# car2.net
KiCad netlist of a schematic drawn in Altium Designer
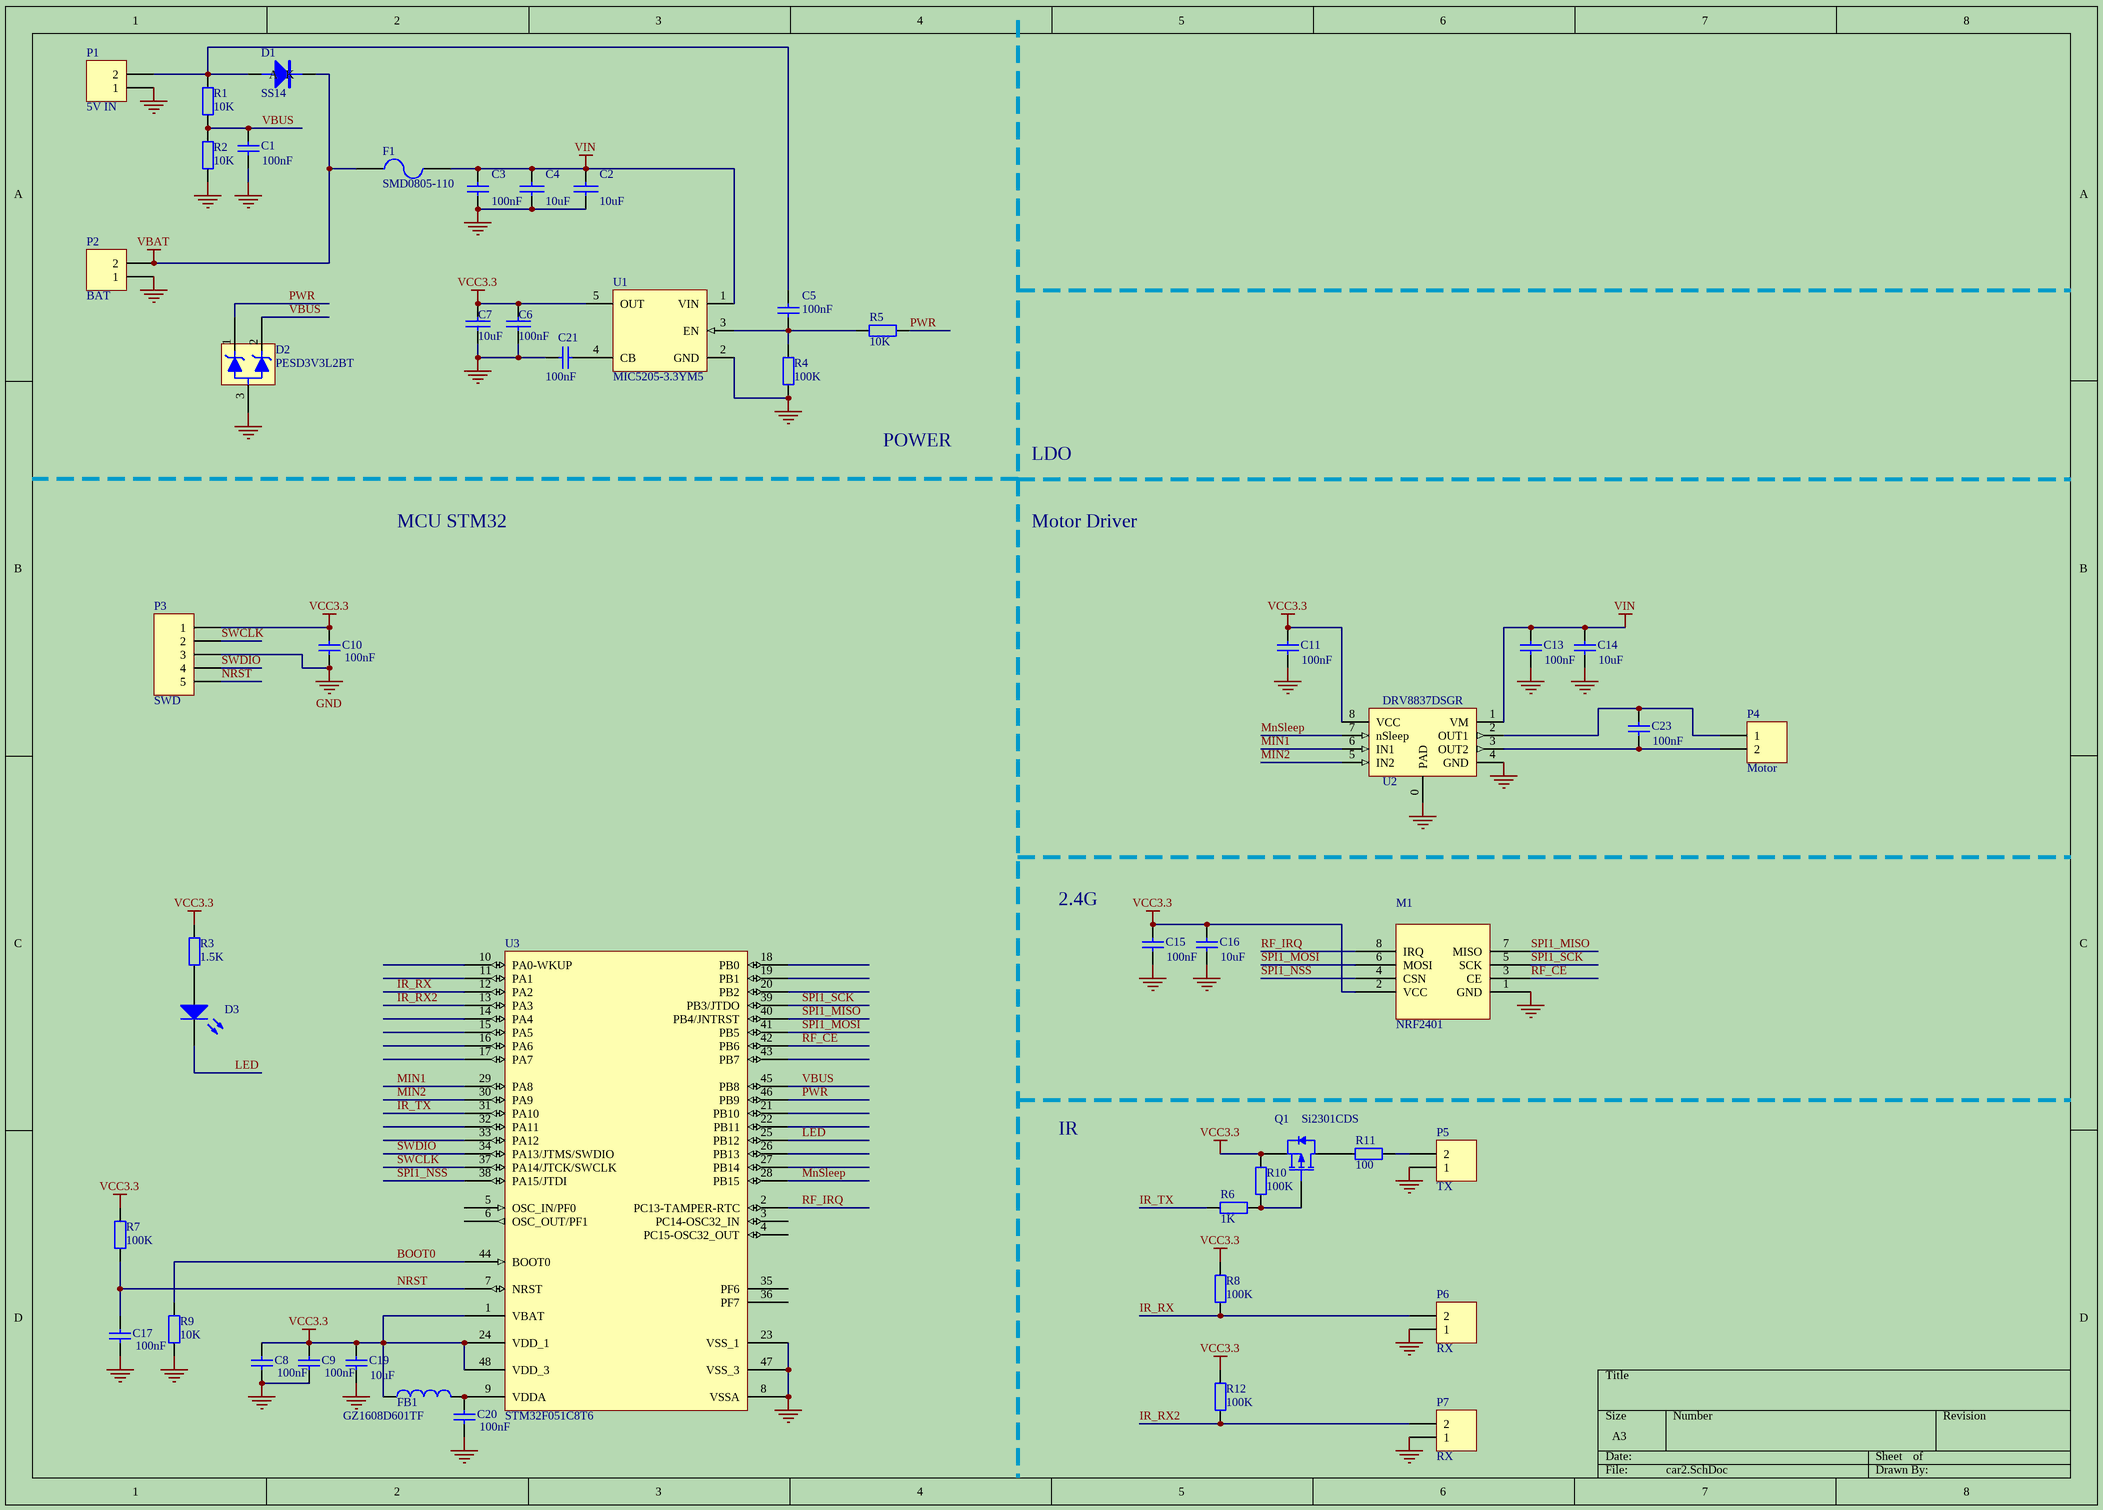
[diagram p0: car2.SchDoc]

(export (version "E")
  (design (tool "Eeschema 10.0.6"))
  (components
    (comp (ref "C1")
      (value "100nF")
      (footprint "C0603")
      (description "Capacitor")
      (fields (field (name "PUBLISHER") "Altium Limited"))
      (libsource (lib "Miscellaneous Devices") (part "Cap"))
    )
    (comp (ref "C2")
      (value "10uF")
      (footprint "C0805")
      (description "Capacitor")
      (libsource (lib "*") (part "CAP"))
    )
    (comp (ref "C3")
      (value "100nF")
      (footprint "C0603")
      (description "Capacitor")
      (fields (field (name "PUBLISHER") "Altium Limited"))
      (libsource (lib "Miscellaneous Devices") (part "Cap"))
    )
    (comp (ref "C4")
      (value "10uF")
      (footprint "C0805")
      (description "Capacitor")
      (libsource (lib "*") (part "CAP"))
    )
    (comp (ref "C5")
      (value "100nF")
      (footprint "C0603")
      (description "Capacitor")
      (fields (field (name "PUBLISHER") "Altium Limited"))
      (libsource (lib "Miscellaneous Devices") (part "Cap"))
    )
    (comp (ref "C6")
      (value "100nF")
      (footprint "C0603")
      (description "Capacitor")
      (libsource (lib "*") (part "CAP"))
    )
    (comp (ref "C7")
      (value "10uF")
      (footprint "C0805")
      (description "Capacitor")
      (libsource (lib "*") (part "CAP"))
    )
    (comp (ref "C8")
      (value "100nF")
      (footprint "C0603")
      (description "Capacitor")
      (fields (field (name "PUBLISHER") "Altium Limited"))
      (libsource (lib "Miscellaneous Devices") (part "Cap"))
    )
    (comp (ref "C9")
      (value "100nF")
      (footprint "C0603")
      (description "Capacitor")
      (fields (field (name "PUBLISHER") "Altium Limited"))
      (libsource (lib "Miscellaneous Devices") (part "Cap"))
    )
    (comp (ref "C10")
      (value "100nF")
      (footprint "C0603")
      (description "Capacitor")
      (fields (field (name "PUBLISHER") "Altium Limited"))
      (libsource (lib "Miscellaneous Devices") (part "Cap"))
    )
    (comp (ref "C11")
      (value "100nF")
      (footprint "C0603")
      (description "Capacitor")
      (fields (field (name "PUBLISHER") "Altium Limited"))
      (libsource (lib "Miscellaneous Devices") (part "Cap"))
    )
    (comp (ref "C13")
      (value "100nF")
      (footprint "C0603")
      (description "Capacitor")
      (fields (field (name "PUBLISHER") "Altium Limited"))
      (libsource (lib "Miscellaneous Devices") (part "Cap"))
    )
    (comp (ref "C14")
      (value "10uF")
      (footprint "C0805")
      (description "Capacitor")
      (fields (field (name "PUBLISHER") "Altium Limited"))
      (libsource (lib "Miscellaneous Devices") (part "Cap"))
    )
    (comp (ref "C15")
      (value "100nF")
      (footprint "C0603")
      (description "Capacitor")
      (fields (field (name "PUBLISHER") "Altium Limited"))
      (libsource (lib "Miscellaneous Devices") (part "Cap"))
    )
    (comp (ref "C16")
      (value "10uF")
      (footprint "C0805")
      (description "Capacitor")
      (fields (field (name "PUBLISHER") "Altium Limited"))
      (libsource (lib "Miscellaneous Devices") (part "Cap"))
    )
    (comp (ref "C17")
      (value "100nF")
      (footprint "C0603")
      (description "Capacitor")
      (fields (field (name "PUBLISHER") "Altium Limited"))
      (libsource (lib "Miscellaneous Devices") (part "Cap"))
    )
    (comp (ref "C19")
      (value "10uF")
      (footprint "C0805")
      (description "Capacitor")
      (fields (field (name "PUBLISHER") "Altium Limited"))
      (libsource (lib "Miscellaneous Devices") (part "Cap"))
    )
    (comp (ref "C20")
      (value "100nF")
      (footprint "C0603")
      (description "Capacitor")
      (fields (field (name "PUBLISHER") "Altium Limited"))
      (libsource (lib "Miscellaneous Devices") (part "Cap"))
    )
    (comp (ref "C21")
      (value "100nF")
      (footprint "C0603")
      (description "Capacitor")
      (fields (field (name "PUBLISHER") "Altium Limited"))
      (libsource (lib "Miscellaneous Devices") (part "Cap"))
    )
    (comp (ref "C23")
      (value "100nF")
      (footprint "C0603")
      (description "Capacitor")
      (fields (field (name "PUBLISHER") "Altium Limited"))
      (libsource (lib "Miscellaneous Devices") (part "Cap"))
    )
    (comp (ref "D1")
      (value "SS14")
      (footprint "LC-SMA(DO-214AC)_S2")
      (description "Diode")
      (libsource (lib "*") (part "DIODE"))
    )
    (comp (ref "D2")
      (value "PESD3V3L2BT")
      (footprint "LC-SOT-23(SOT-23-3)")
      (description "TVS")
      (libsource (lib "*") (part "ZENER2"))
    )
    (comp (ref "D3")
      (value "LEDV1")
      (footprint "LC-0603_LED_S4")
      (description "Typical RED, GREEN, YELLOW, AMBER GaAs LED")
      (fields (field (name "PUBLISHER") "Altium Limited"))
      (libsource (lib "Miscellaneous Devices") (part "LED2"))
    )
    (comp (ref "F1")
      (value "SMD0805-110")
      (footprint "R0805")
      (description "Fuse")
      (fields (field (name "PUBLISHER") "Altium Limited"))
      (libsource (lib "Miscellaneous Devices") (part "Fuse 2"))
    )
    (comp (ref "FB1") (value "GZ1608D601TF") (footprint "R0603") (libsource (lib "*") (part "INDUCTOR1")))
    (comp (ref "M1") (value "NRF2401") (footprint "HDR2X4") (libsource (lib "*") (part "NRF2401")))
    (comp (ref "P1")
      (value "5V IN")
      (footprint "PH-2Y")
      (description "Header, 2-Pin")
      (fields (field (name "PUBLISHER") "Altium Limited"))
      (libsource (lib "") (part "Header 2_2"))
    )
    (comp (ref "P2")
      (value "BAT")
      (footprint "PH-2Y")
      (description "Header, 2-Pin")
      (fields (field (name "PUBLISHER") "Altium Limited"))
      (libsource (lib "") (part "Header 2_2"))
    )
    (comp (ref "P3")
      (value "SWD")
      (footprint "HDR1X5")
      (description "Header, 5-Pin")
      (fields (field (name "PUBLISHER") "Altium Limited"))
      (libsource (lib "Miscellaneous Connectors") (part "Header 5"))
    )
    (comp (ref "P4")
      (value "Motor")
      (footprint "PH-2Y")
      (description "Header, 2-Pin")
      (fields (field (name "PUBLISHER") "Altium Limited"))
      (libsource (lib "Miscellaneous Connectors") (part "Header 2"))
    )
    (comp (ref "P5")
      (value "TX")
      (footprint "PH-2Y")
      (description "Header, 2-Pin")
      (fields (field (name "PUBLISHER") "Altium Limited"))
      (libsource (lib "") (part "Header 2_1"))
    )
    (comp (ref "P6")
      (value "RX")
      (footprint "PH-2Y")
      (description "Header, 2-Pin")
      (fields (field (name "PUBLISHER") "Altium Limited"))
      (libsource (lib "") (part "Header 2_1"))
    )
    (comp (ref "P7")
      (value "RX")
      (footprint "PH-2Y")
      (description "Header, 2-Pin")
      (fields (field (name "PUBLISHER") "Altium Limited"))
      (libsource (lib "") (part "Header 2_1"))
    )
    (comp (ref "Q1")
      (value "Si2301CDS")
      (footprint "LC-SOT-23(SOT-23-3)")
      (description "P-channel Enhancement Mode MOSFET")
      (fields (field (name "PUBLISHER") "Altium Limited"))
      (libsource (lib "Philips Discrete MOSFET - Low Power") (part "BSH201"))
    )
    (comp (ref "R1")
      (value "10K")
      (footprint "R0603")
      (description "Resistor")
      (fields (field (name "PUBLISHER") "Altium Limited"))
      (libsource (lib "Miscellaneous Devices") (part "Res2"))
    )
    (comp (ref "R2")
      (value "10K")
      (footprint "R0603")
      (description "Resistor")
      (fields (field (name "PUBLISHER") "Altium Limited"))
      (libsource (lib "Miscellaneous Devices") (part "Res2"))
    )
    (comp (ref "R3")
      (value "1.5K")
      (footprint "R0603")
      (description "Resistor")
      (fields (field (name "PUBLISHER") "Altium Limited"))
      (libsource (lib "Miscellaneous Devices") (part "Res2"))
    )
    (comp (ref "R4")
      (value "100K")
      (footprint "R0603")
      (description "Resistor")
      (fields (field (name "PUBLISHER") "Altium Limited"))
      (libsource (lib "Miscellaneous Devices") (part "Res2"))
    )
    (comp (ref "R5")
      (value "10K")
      (footprint "R0603")
      (description "Resistor")
      (fields (field (name "PUBLISHER") "Altium Limited"))
      (libsource (lib "") (part "Res2_3"))
    )
    (comp (ref "R6")
      (value "1K")
      (footprint "R0603")
      (description "Resistor")
      (fields (field (name "PUBLISHER") "Altium Limited"))
      (libsource (lib "") (part "Res2_3"))
    )
    (comp (ref "R7")
      (value "100K")
      (footprint "R0603")
      (description "Resistor")
      (fields (field (name "PUBLISHER") "Altium Limited"))
      (libsource (lib "Miscellaneous Devices") (part "Res2"))
    )
    (comp (ref "R8")
      (value "100K")
      (footprint "R0603")
      (description "Resistor")
      (fields (field (name "PUBLISHER") "Altium Limited"))
      (libsource (lib "") (part "Res2_1"))
    )
    (comp (ref "R9")
      (value "10K")
      (footprint "R0603")
      (description "Resistor")
      (fields (field (name "PUBLISHER") "Altium Limited"))
      (libsource (lib "Miscellaneous Devices") (part "Res2"))
    )
    (comp (ref "R10")
      (value "100K")
      (footprint "R0603")
      (description "Resistor")
      (fields (field (name "PUBLISHER") "Altium Limited"))
      (libsource (lib "") (part "Res2_1"))
    )
    (comp (ref "R11")
      (value "100")
      (footprint "R0603")
      (description "Resistor")
      (fields (field (name "PUBLISHER") "Altium Limited"))
      (libsource (lib "") (part "Res2_2"))
    )
    (comp (ref "R12")
      (value "100K")
      (footprint "R0603")
      (description "Resistor")
      (fields (field (name "PUBLISHER") "Altium Limited"))
      (libsource (lib "") (part "Res2_1"))
    )
    (comp (ref "U1")
      (value "MIC5205-3.3YM5")
      (footprint "LC-SOT-23-5")
      (description "150mA Low-Noise LDO Regulator")
      (libsource (lib "Sheet1") (part "MIC5205"))
    )
    (comp (ref "U2")
      (value "DRV8837DSGR")
      (footprint "LC-WSON-8_2x2mm - DRV8837")
      (description "Low-Voltage H-Bridge Driver")
      (libsource (lib "GW") (part "DRV883x"))
    )
    (comp (ref "U3")
      (value "STM32F051C8T6")
      (footprint "LC-LQFP-48_7x7x05P")
      (description "STM32 ARM-based 32-bit MCU with 64 Kbytes Flash, 48-pin LQFP, Industrial Temperature")
      (fields (field (name "PUBLISHER") "Altium Limited"))
      (libsource (lib "PRA1-SINGLE-POWER-V1.0") (part "STM32F51C8T6"))
    )
  )
  (nets
    (net (code "1") (name "/BOOT0") (class "Default")
      (node (ref "R9") (pin "2") (pinfunction "2_2") (pintype "passive"))
      (node (ref "U3") (pin "44") (pinfunction "BOOT0_44") (pintype "input"))
    )
    (net (code "2") (name "/IR_RX") (class "Default")
      (node (ref "P6") (pin "2") (pinfunction "2_2") (pintype "passive"))
      (node (ref "R8") (pin "2") (pinfunction "2_2") (pintype "passive"))
      (node (ref "U3") (pin "12") (pinfunction "PA2_12") (pintype "bidirectional"))
    )
    (net (code "3") (name "/IR_RX2") (class "Default")
      (node (ref "P7") (pin "2") (pinfunction "2_2") (pintype "passive"))
      (node (ref "R12") (pin "2") (pinfunction "2_2") (pintype "passive"))
      (node (ref "U3") (pin "13") (pinfunction "PA3_13") (pintype "bidirectional"))
    )
    (net (code "4") (name "/IR_TX") (class "Default")
      (node (ref "R6") (pin "2") (pinfunction "2_2") (pintype "passive"))
      (node (ref "U3") (pin "31") (pinfunction "PA10_31") (pintype "bidirectional"))
    )
    (net (code "5") (name "/LED") (class "Default")
      (node (ref "D3") (pin "K") (pinfunction "K_K") (pintype "passive"))
      (node (ref "U3") (pin "25") (pinfunction "PB12_25") (pintype "bidirectional"))
    )
    (net (code "6") (name "/MIN1") (class "Default")
      (node (ref "U2") (pin "6") (pinfunction "IN1_6") (pintype "input"))
      (node (ref "U3") (pin "29") (pinfunction "PA8_29") (pintype "bidirectional"))
    )
    (net (code "7") (name "/MIN2") (class "Default")
      (node (ref "U2") (pin "5") (pinfunction "IN2_5") (pintype "input"))
      (node (ref "U3") (pin "30") (pinfunction "PA9_30") (pintype "bidirectional"))
    )
    (net (code "8") (name "/MnSleep") (class "Default")
      (node (ref "U2") (pin "7") (pinfunction "nSleep_7") (pintype "input"))
      (node (ref "U3") (pin "28") (pinfunction "PB15_28") (pintype "bidirectional"))
    )
    (net (code "9") (name "/NRST") (class "Default")
      (node (ref "C17") (pin "2") (pinfunction "2_2") (pintype "passive"))
      (node (ref "P3") (pin "5") (pinfunction "5_5") (pintype "passive"))
      (node (ref "R7") (pin "1") (pinfunction "1_1") (pintype "passive"))
      (node (ref "U3") (pin "7") (pinfunction "NRST_7") (pintype "bidirectional"))
    )
    (net (code "10") (name "/PWR") (class "Default")
      (node (ref "D2") (pin "1") (pinfunction "1_1") (pintype "passive"))
      (node (ref "R5") (pin "1") (pinfunction "1_1") (pintype "passive"))
      (node (ref "U3") (pin "46") (pinfunction "PB9_46") (pintype "bidirectional"))
    )
    (net (code "11") (name "/RF_CE") (class "Default")
      (node (ref "M1") (pin "3") (pinfunction "CE_3") (pintype "passive"))
      (node (ref "U3") (pin "42") (pinfunction "PB6_42") (pintype "bidirectional"))
    )
    (net (code "12") (name "/RF_IRQ") (class "Default")
      (node (ref "M1") (pin "8") (pinfunction "IRQ_8") (pintype "passive"))
      (node (ref "U3") (pin "2") (pinfunction "PC13-TAMPER-RTC_2") (pintype "bidirectional"))
    )
    (net (code "13") (name "/SPI1_MISO") (class "Default")
      (node (ref "M1") (pin "7") (pinfunction "MISO_7") (pintype "passive"))
      (node (ref "U3") (pin "40") (pinfunction "PB4/JNTRST_40") (pintype "bidirectional"))
    )
    (net (code "14") (name "/SPI1_MOSI") (class "Default")
      (node (ref "M1") (pin "6") (pinfunction "MOSI_6") (pintype "passive"))
      (node (ref "U3") (pin "41") (pinfunction "PB5_41") (pintype "bidirectional"))
    )
    (net (code "15") (name "/SPI1_NSS") (class "Default")
      (node (ref "M1") (pin "4") (pinfunction "CSN_4") (pintype "passive"))
      (node (ref "U3") (pin "38") (pinfunction "PA15/JTDI_38") (pintype "bidirectional"))
    )
    (net (code "16") (name "/SPI1_SCK") (class "Default")
      (node (ref "M1") (pin "5") (pinfunction "SCK_5") (pintype "passive"))
      (node (ref "U3") (pin "39") (pinfunction "PB3/JTDO_39") (pintype "bidirectional"))
    )
    (net (code "17") (name "/SWCLK") (class "Default")
      (node (ref "P3") (pin "2") (pinfunction "2_2") (pintype "passive"))
      (node (ref "U3") (pin "37") (pinfunction "PA14/JTCK/SWCLK_37") (pintype "bidirectional"))
    )
    (net (code "18") (name "/SWDIO") (class "Default")
      (node (ref "P3") (pin "4") (pinfunction "4_4") (pintype "passive"))
      (node (ref "U3") (pin "34") (pinfunction "PA13/JTMS/SWDIO_34") (pintype "bidirectional"))
    )
    (net (code "19") (name "/VBUS") (class "Default")
      (node (ref "C1") (pin "2") (pinfunction "2_2") (pintype "passive"))
      (node (ref "D2") (pin "2") (pinfunction "2_2") (pintype "passive"))
      (node (ref "R1") (pin "1") (pinfunction "1_1") (pintype "passive"))
      (node (ref "R2") (pin "2") (pinfunction "2_2") (pintype "passive"))
      (node (ref "U3") (pin "45") (pinfunction "PB8_45") (pintype "bidirectional"))
    )
    (net (code "20") (name "GND") (class "Default")
      (node (ref "C1") (pin "1") (pinfunction "1_1") (pintype "passive"))
      (node (ref "C10") (pin "2") (pinfunction "2_2") (pintype "passive"))
      (node (ref "C11") (pin "1") (pinfunction "1_1") (pintype "passive"))
      (node (ref "C13") (pin "1") (pinfunction "1_1") (pintype "passive"))
      (node (ref "C14") (pin "1") (pinfunction "1_1") (pintype "passive"))
      (node (ref "C15") (pin "1") (pinfunction "1_1") (pintype "passive"))
      (node (ref "C16") (pin "1") (pinfunction "1_1") (pintype "passive"))
      (node (ref "C17") (pin "1") (pinfunction "1_1") (pintype "passive"))
      (node (ref "C19") (pin "1") (pinfunction "1_1") (pintype "passive"))
      (node (ref "C2") (pin "2") (pinfunction "2_2") (pintype "passive"))
      (node (ref "C20") (pin "1") (pinfunction "1_1") (pintype "passive"))
      (node (ref "C21") (pin "2") (pinfunction "2_2") (pintype "passive"))
      (node (ref "C3") (pin "1") (pinfunction "1_1") (pintype "passive"))
      (node (ref "C4") (pin "2") (pinfunction "2_2") (pintype "passive"))
      (node (ref "C6") (pin "2") (pinfunction "2_2") (pintype "passive"))
      (node (ref "C7") (pin "2") (pinfunction "2_2") (pintype "passive"))
      (node (ref "C8") (pin "1") (pinfunction "1_1") (pintype "passive"))
      (node (ref "C9") (pin "1") (pinfunction "1_1") (pintype "passive"))
      (node (ref "D2") (pin "3") (pinfunction "3_3") (pintype "passive"))
      (node (ref "M1") (pin "1") (pinfunction "GND_1") (pintype "passive"))
      (node (ref "P1") (pin "1") (pinfunction "1_1") (pintype "passive"))
      (node (ref "P2") (pin "1") (pinfunction "1_1") (pintype "passive"))
      (node (ref "P3") (pin "3") (pinfunction "3_3") (pintype "passive"))
      (node (ref "P5") (pin "1") (pinfunction "1_1") (pintype "passive"))
      (node (ref "P6") (pin "1") (pinfunction "1_1") (pintype "passive"))
      (node (ref "P7") (pin "1") (pinfunction "1_1") (pintype "passive"))
      (node (ref "R2") (pin "1") (pinfunction "1_1") (pintype "passive"))
      (node (ref "R4") (pin "1") (pinfunction "1_1") (pintype "passive"))
      (node (ref "R9") (pin "1") (pinfunction "1_1") (pintype "passive"))
      (node (ref "U1") (pin "2") (pinfunction "GND_2") (pintype "power_in"))
      (node (ref "U2") (pin "0") (pinfunction "PAD_0") (pintype "power_in"))
      (node (ref "U2") (pin "4") (pinfunction "GND_4") (pintype "power_in"))
      (node (ref "U3") (pin "23") (pinfunction "VSS_1_23") (pintype "power_in"))
      (node (ref "U3") (pin "47") (pinfunction "VSS_3_47") (pintype "power_in"))
      (node (ref "U3") (pin "8") (pinfunction "VSSA_8") (pintype "power_in"))
    )
    (net (code "21") (name "Net-(D1-A)") (class "Default")
      (node (ref "C5") (pin "2") (pinfunction "2_2") (pintype "passive"))
      (node (ref "D1") (pin "1") (pinfunction "A_1") (pintype "passive"))
      (node (ref "P1") (pin "2") (pinfunction "2_2") (pintype "passive"))
      (node (ref "R1") (pin "2") (pinfunction "2_2") (pintype "passive"))
    )
    (net (code "22") (name "Net-(D3-PadA)") (class "Default")
      (node (ref "D3") (pin "A") (pinfunction "A_A") (pintype "passive"))
      (node (ref "R3") (pin "1") (pinfunction "1_1") (pintype "passive"))
    )
    (net (code "23") (name "Net-(P5-Pad2)") (class "Default")
      (node (ref "P5") (pin "2") (pinfunction "2_2") (pintype "passive"))
      (node (ref "R11") (pin "2") (pinfunction "2_2") (pintype "passive"))
    )
    (net (code "24") (name "Net-(Q1-D)") (class "Default")
      (node (ref "Q1") (pin "3") (pinfunction "D_3") (pintype "passive"))
      (node (ref "R11") (pin "1") (pinfunction "1_1") (pintype "passive"))
    )
    (net (code "25") (name "Net-(Q1-G)") (class "Default")
      (node (ref "Q1") (pin "1") (pinfunction "G_1") (pintype "passive"))
      (node (ref "R10") (pin "2") (pinfunction "2_2") (pintype "passive"))
      (node (ref "R6") (pin "1") (pinfunction "1_1") (pintype "passive"))
    )
    (net (code "26") (name "Net-(U1-CB)") (class "Default")
      (node (ref "C21") (pin "1") (pinfunction "1_1") (pintype "passive"))
      (node (ref "U1") (pin "4") (pinfunction "CB_4") (pintype "passive"))
    )
    (net (code "27") (name "Net-(U1-EN)") (class "Default")
      (node (ref "C5") (pin "1") (pinfunction "1_1") (pintype "passive"))
      (node (ref "R4") (pin "2") (pinfunction "2_2") (pintype "passive"))
      (node (ref "R5") (pin "2") (pinfunction "2_2") (pintype "passive"))
      (node (ref "U1") (pin "3") (pinfunction "EN_3") (pintype "input"))
    )
    (net (code "28") (name "Net-(U2-OUT1)") (class "Default")
      (node (ref "C23") (pin "2") (pinfunction "2_2") (pintype "passive"))
      (node (ref "P4") (pin "1") (pinfunction "1_1") (pintype "passive"))
      (node (ref "U2") (pin "2") (pinfunction "OUT1_2") (pintype "output"))
    )
    (net (code "29") (name "Net-(U2-OUT2)") (class "Default")
      (node (ref "C23") (pin "1") (pinfunction "1_1") (pintype "passive"))
      (node (ref "P4") (pin "2") (pinfunction "2_2") (pintype "passive"))
      (node (ref "U2") (pin "3") (pinfunction "OUT2_3") (pintype "output"))
    )
    (net (code "30") (name "Net-(U3-VDDA)") (class "Default")
      (node (ref "C20") (pin "2") (pinfunction "2_2") (pintype "passive"))
      (node (ref "FB1") (pin "2") (pinfunction "2_2") (pintype "passive"))
      (node (ref "U3") (pin "9") (pinfunction "VDDA_9") (pintype "power_in"))
    )
    (net (code "31") (name "VBAT") (class "Default")
      (node (ref "D1") (pin "2") (pinfunction "K_2") (pintype "passive"))
      (node (ref "F1") (pin "1") (pinfunction "1_1") (pintype "passive"))
      (node (ref "P2") (pin "2") (pinfunction "2_2") (pintype "passive"))
    )
    (net (code "32") (name "VCC3.3") (class "Default")
      (node (ref "C10") (pin "1") (pinfunction "1_1") (pintype "passive"))
      (node (ref "C11") (pin "2") (pinfunction "2_2") (pintype "passive"))
      (node (ref "C15") (pin "2") (pinfunction "2_2") (pintype "passive"))
      (node (ref "C16") (pin "2") (pinfunction "2_2") (pintype "passive"))
      (node (ref "C19") (pin "2") (pinfunction "2_2") (pintype "passive"))
      (node (ref "C6") (pin "1") (pinfunction "1_1") (pintype "passive"))
      (node (ref "C7") (pin "1") (pinfunction "1_1") (pintype "passive"))
      (node (ref "C8") (pin "2") (pinfunction "2_2") (pintype "passive"))
      (node (ref "C9") (pin "2") (pinfunction "2_2") (pintype "passive"))
      (node (ref "FB1") (pin "1") (pinfunction "1_1") (pintype "passive"))
      (node (ref "M1") (pin "2") (pinfunction "VCC_2") (pintype "passive"))
      (node (ref "P3") (pin "1") (pinfunction "1_1") (pintype "passive"))
      (node (ref "Q1") (pin "2") (pinfunction "S_2") (pintype "passive"))
      (node (ref "R10") (pin "1") (pinfunction "1_1") (pintype "passive"))
      (node (ref "R12") (pin "1") (pinfunction "1_1") (pintype "passive"))
      (node (ref "R3") (pin "2") (pinfunction "2_2") (pintype "passive"))
      (node (ref "R7") (pin "2") (pinfunction "2_2") (pintype "passive"))
      (node (ref "R8") (pin "1") (pinfunction "1_1") (pintype "passive"))
      (node (ref "U1") (pin "5") (pinfunction "OUT_5") (pintype "power_in"))
      (node (ref "U2") (pin "8") (pinfunction "VCC_8") (pintype "power_in"))
      (node (ref "U3") (pin "1") (pinfunction "VBAT_1") (pintype "power_in"))
      (node (ref "U3") (pin "24") (pinfunction "VDD_1_24") (pintype "power_in"))
      (node (ref "U3") (pin "48") (pinfunction "VDD_3_48") (pintype "power_in"))
    )
    (net (code "33") (name "VIN") (class "Default")
      (node (ref "C13") (pin "2") (pinfunction "2_2") (pintype "passive"))
      (node (ref "C14") (pin "2") (pinfunction "2_2") (pintype "passive"))
      (node (ref "C2") (pin "1") (pinfunction "1_1") (pintype "passive"))
      (node (ref "C3") (pin "2") (pinfunction "2_2") (pintype "passive"))
      (node (ref "C4") (pin "1") (pinfunction "1_1") (pintype "passive"))
      (node (ref "F1") (pin "2") (pinfunction "2_2") (pintype "passive"))
      (node (ref "U1") (pin "1") (pinfunction "VIN_1") (pintype "power_in"))
      (node (ref "U2") (pin "1") (pinfunction "VM_1") (pintype "power_in"))
    )
    (net (code "34") (name "unconnected-(U3-OSC_IN{slash}PF0-Pad5)") (class "Default")
      (node (ref "U3") (pin "5") (pinfunction "OSC_IN/PF0_5") (pintype "input"))
    )
    (net (code "35") (name "unconnected-(U3-OSC_OUT{slash}PF1-Pad6)") (class "Default")
      (node (ref "U3") (pin "6") (pinfunction "OSC_OUT/PF1_6") (pintype "output"))
    )
    (net (code "36") (name "unconnected-(U3-PA0-WKUP-Pad10)") (class "Default")
      (node (ref "U3") (pin "10") (pinfunction "PA0-WKUP_10") (pintype "bidirectional"))
    )
    (net (code "37") (name "unconnected-(U3-PA1-Pad11)") (class "Default")
      (node (ref "U3") (pin "11") (pinfunction "PA1_11") (pintype "bidirectional"))
    )
    (net (code "38") (name "unconnected-(U3-PA4-Pad14)") (class "Default")
      (node (ref "U3") (pin "14") (pinfunction "PA4_14") (pintype "bidirectional"))
    )
    (net (code "39") (name "unconnected-(U3-PA5-Pad15)") (class "Default")
      (node (ref "U3") (pin "15") (pinfunction "PA5_15") (pintype "bidirectional"))
    )
    (net (code "40") (name "unconnected-(U3-PA6-Pad16)") (class "Default")
      (node (ref "U3") (pin "16") (pinfunction "PA6_16") (pintype "bidirectional"))
    )
    (net (code "41") (name "unconnected-(U3-PA7-Pad17)") (class "Default")
      (node (ref "U3") (pin "17") (pinfunction "PA7_17") (pintype "bidirectional"))
    )
    (net (code "42") (name "unconnected-(U3-PA11-Pad32)") (class "Default")
      (node (ref "U3") (pin "32") (pinfunction "PA11_32") (pintype "bidirectional"))
    )
    (net (code "43") (name "unconnected-(U3-PA12-Pad33)") (class "Default")
      (node (ref "U3") (pin "33") (pinfunction "PA12_33") (pintype "bidirectional"))
    )
    (net (code "44") (name "unconnected-(U3-PB0-Pad18)") (class "Default")
      (node (ref "U3") (pin "18") (pinfunction "PB0_18") (pintype "bidirectional"))
    )
    (net (code "45") (name "unconnected-(U3-PB1-Pad19)") (class "Default")
      (node (ref "U3") (pin "19") (pinfunction "PB1_19") (pintype "bidirectional"))
    )
    (net (code "46") (name "unconnected-(U3-PB2-Pad20)") (class "Default")
      (node (ref "U3") (pin "20") (pinfunction "PB2_20") (pintype "bidirectional"))
    )
    (net (code "47") (name "unconnected-(U3-PB7-Pad43)") (class "Default")
      (node (ref "U3") (pin "43") (pinfunction "PB7_43") (pintype "bidirectional"))
    )
    (net (code "48") (name "unconnected-(U3-PB10-Pad21)") (class "Default")
      (node (ref "U3") (pin "21") (pinfunction "PB10_21") (pintype "bidirectional"))
    )
    (net (code "49") (name "unconnected-(U3-PB11-Pad22)") (class "Default")
      (node (ref "U3") (pin "22") (pinfunction "PB11_22") (pintype "bidirectional"))
    )
    (net (code "50") (name "unconnected-(U3-PB13-Pad26)") (class "Default")
      (node (ref "U3") (pin "26") (pinfunction "PB13_26") (pintype "bidirectional"))
    )
    (net (code "51") (name "unconnected-(U3-PB14-Pad27)") (class "Default")
      (node (ref "U3") (pin "27") (pinfunction "PB14_27") (pintype "bidirectional"))
    )
    (net (code "52") (name "unconnected-(U3-PC14-OSC32_IN-Pad3)") (class "Default")
      (node (ref "U3") (pin "3") (pinfunction "PC14-OSC32_IN_3") (pintype "bidirectional"))
    )
    (net (code "53") (name "unconnected-(U3-PC15-OSC32_OUT-Pad4)") (class "Default")
      (node (ref "U3") (pin "4") (pinfunction "PC15-OSC32_OUT_4") (pintype "bidirectional"))
    )
    (net (code "54") (name "unconnected-(U3-PF6-Pad35)") (class "Default")
      (node (ref "U3") (pin "35") (pinfunction "PF6_35") (pintype "power_in"))
    )
    (net (code "55") (name "unconnected-(U3-PF7-Pad36)") (class "Default")
      (node (ref "U3") (pin "36") (pinfunction "PF7_36") (pintype "power_in"))
    )
  )
)
